# Kopfh_rerverst_rker_AmpBoard_Rev_1_0.net
KiCad netlist of a schematic drawn in EAGLE
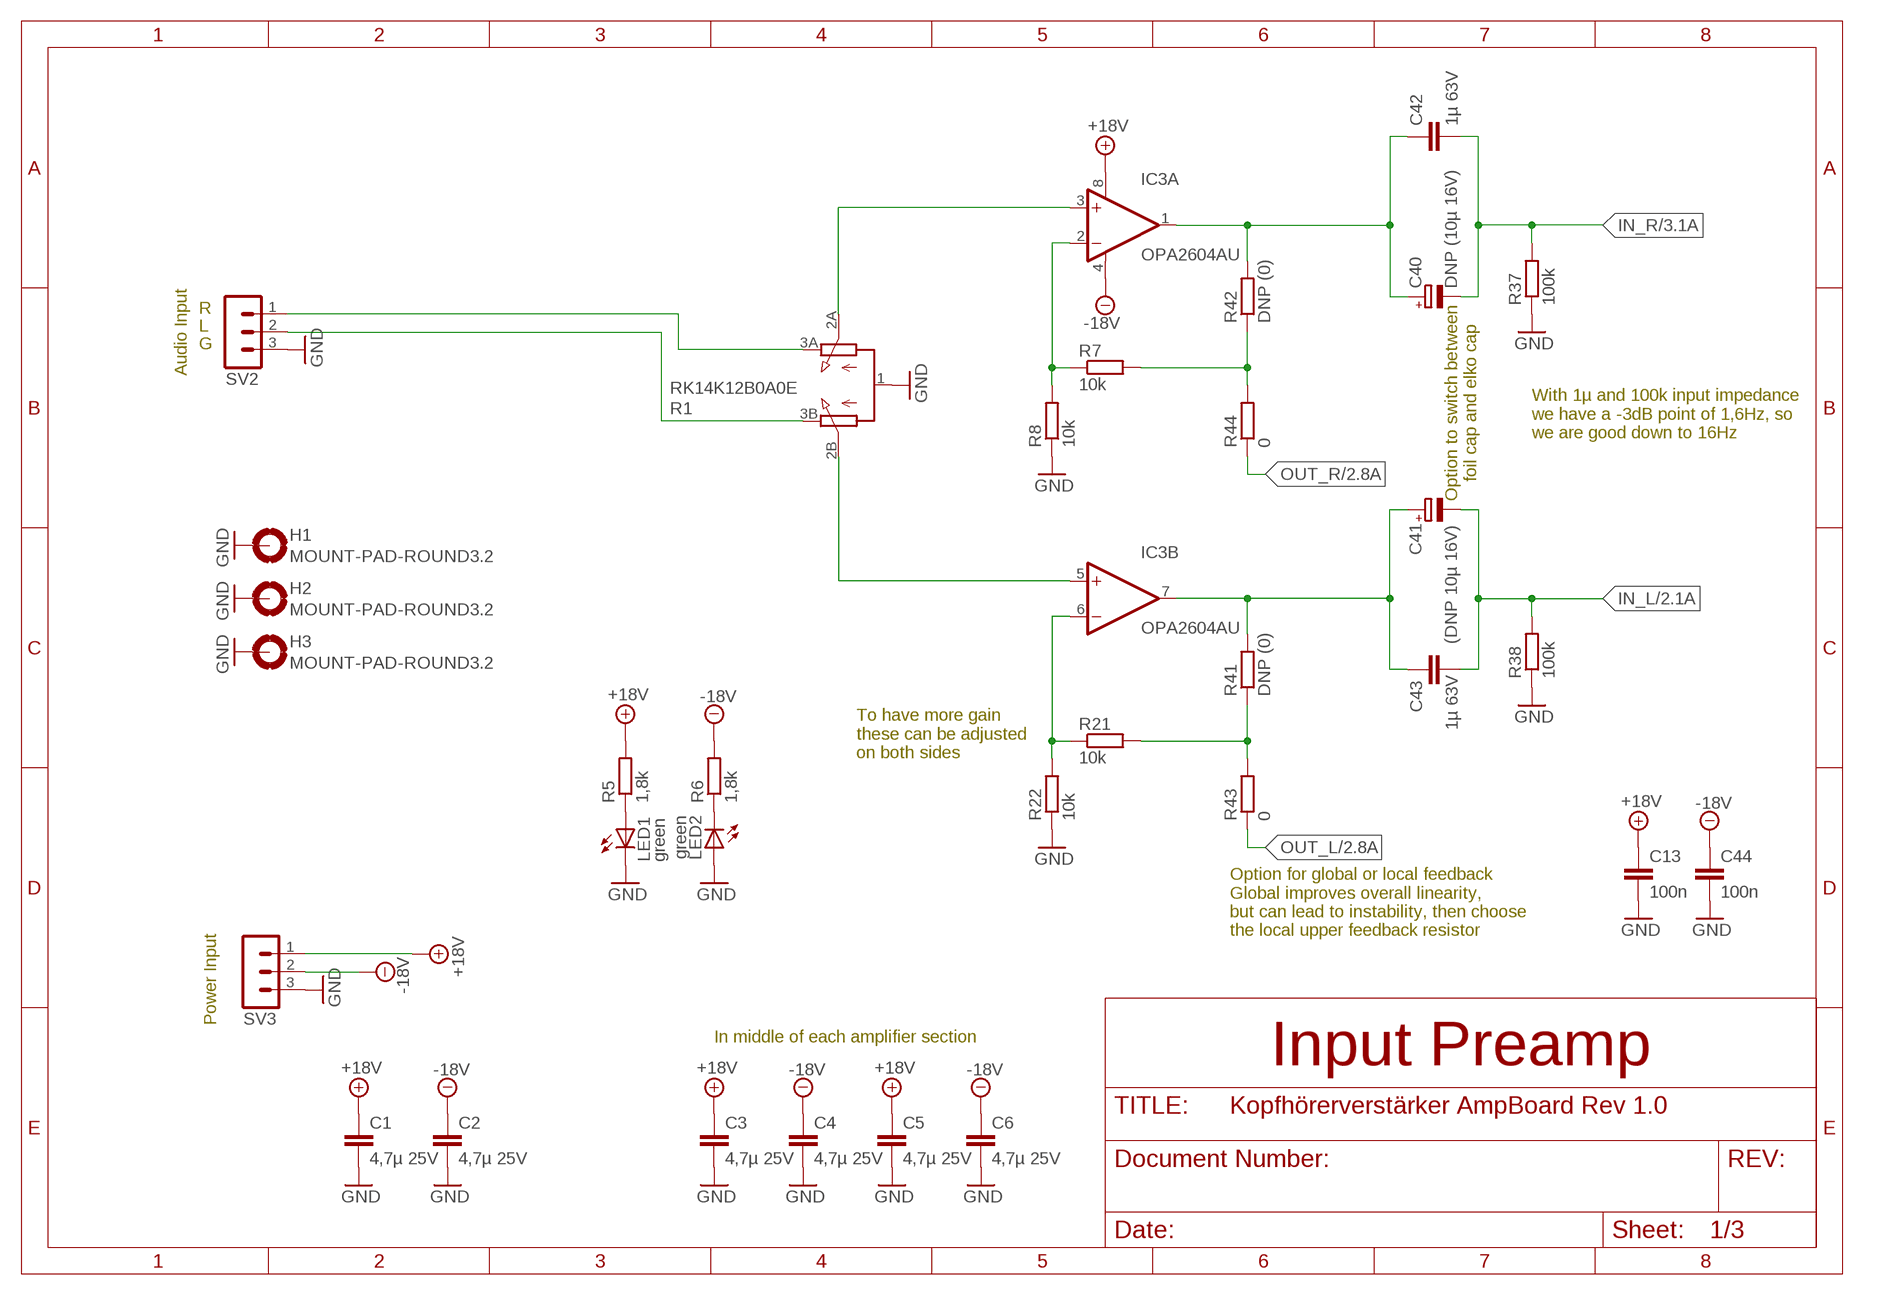
[diagram p0: schematic, sheet 1]
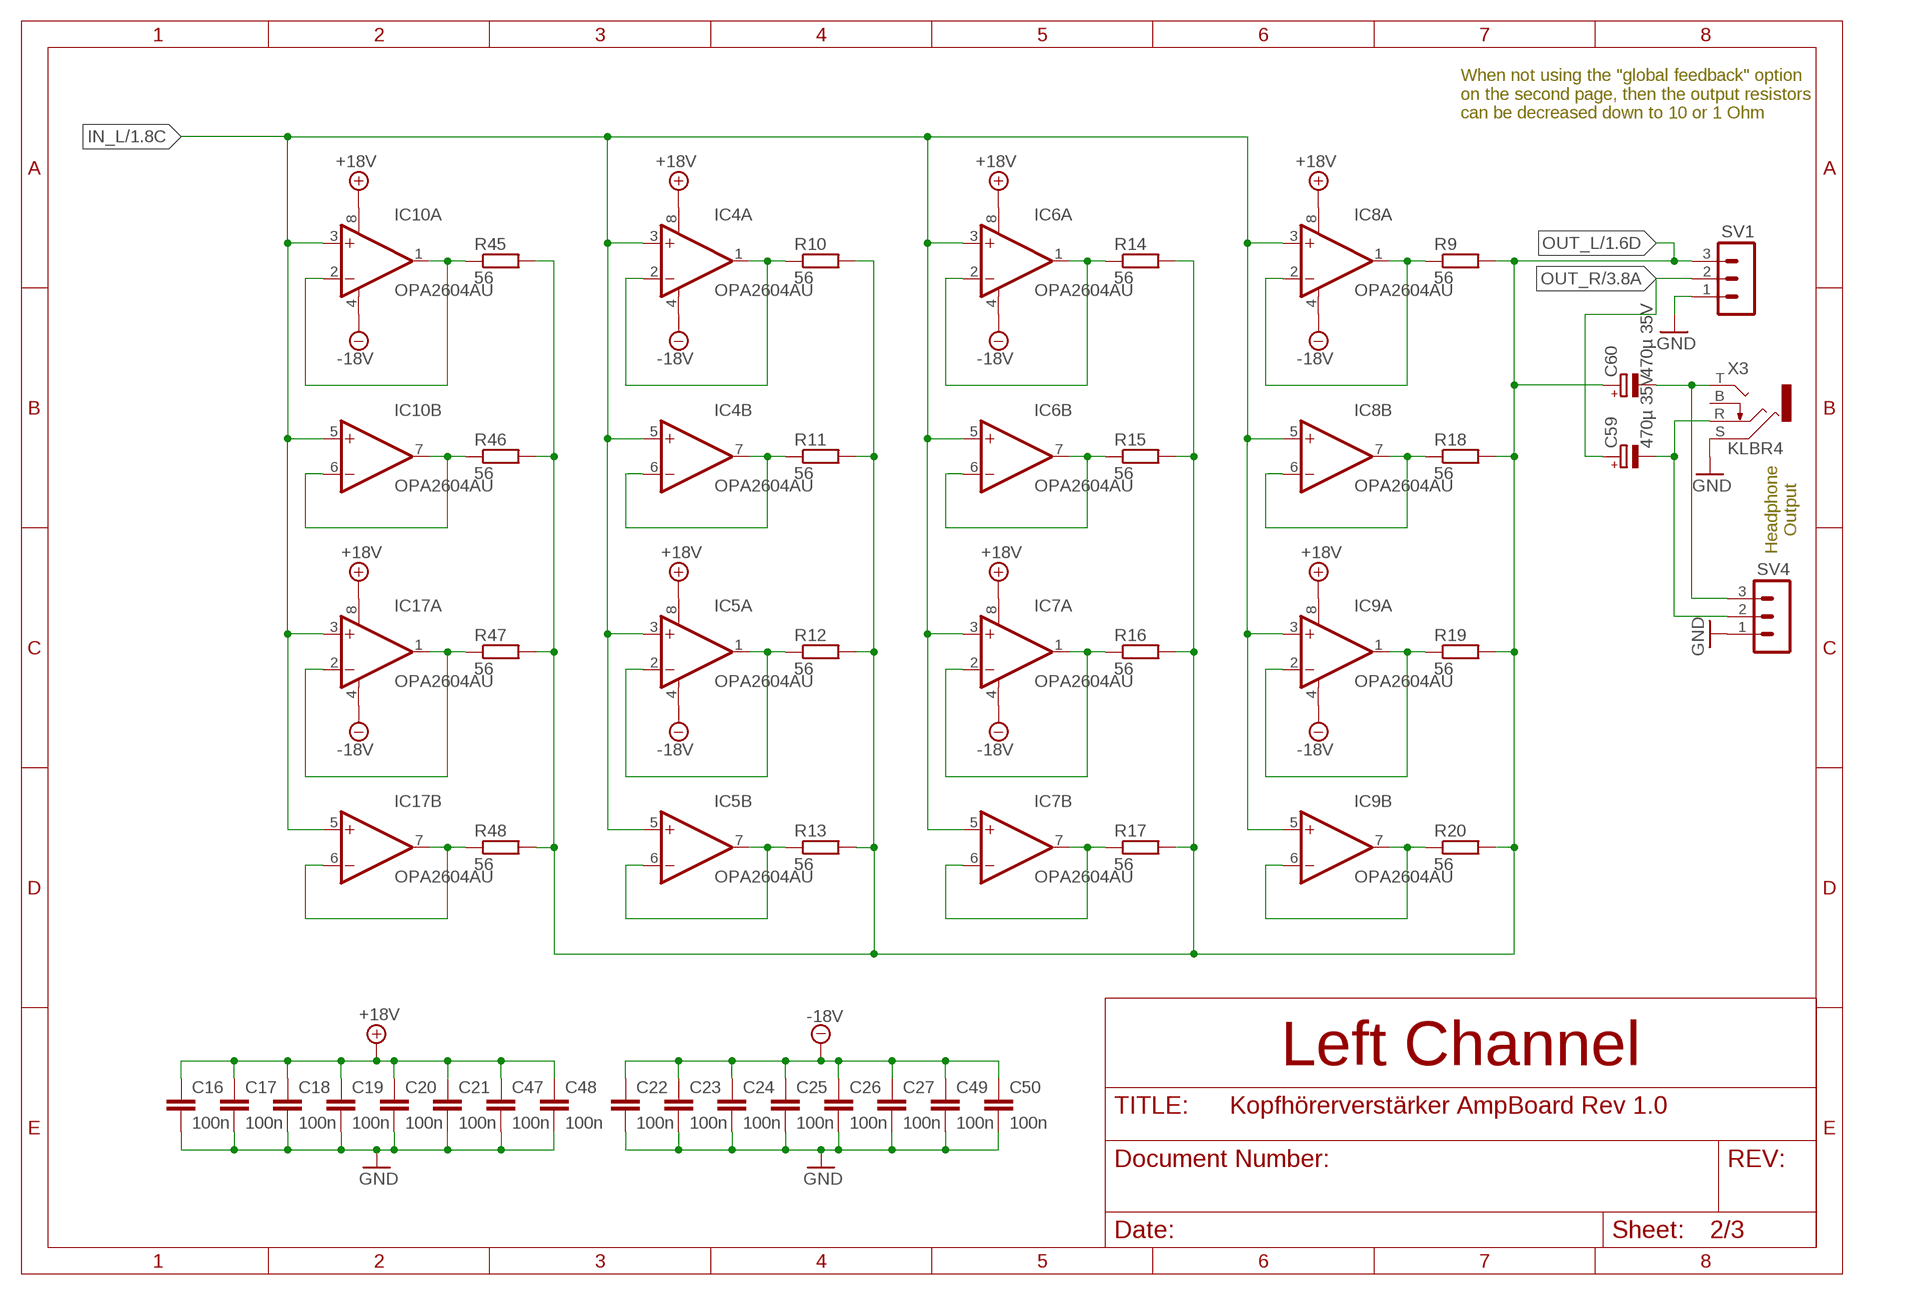
[diagram p1: schematic, sheet 2]
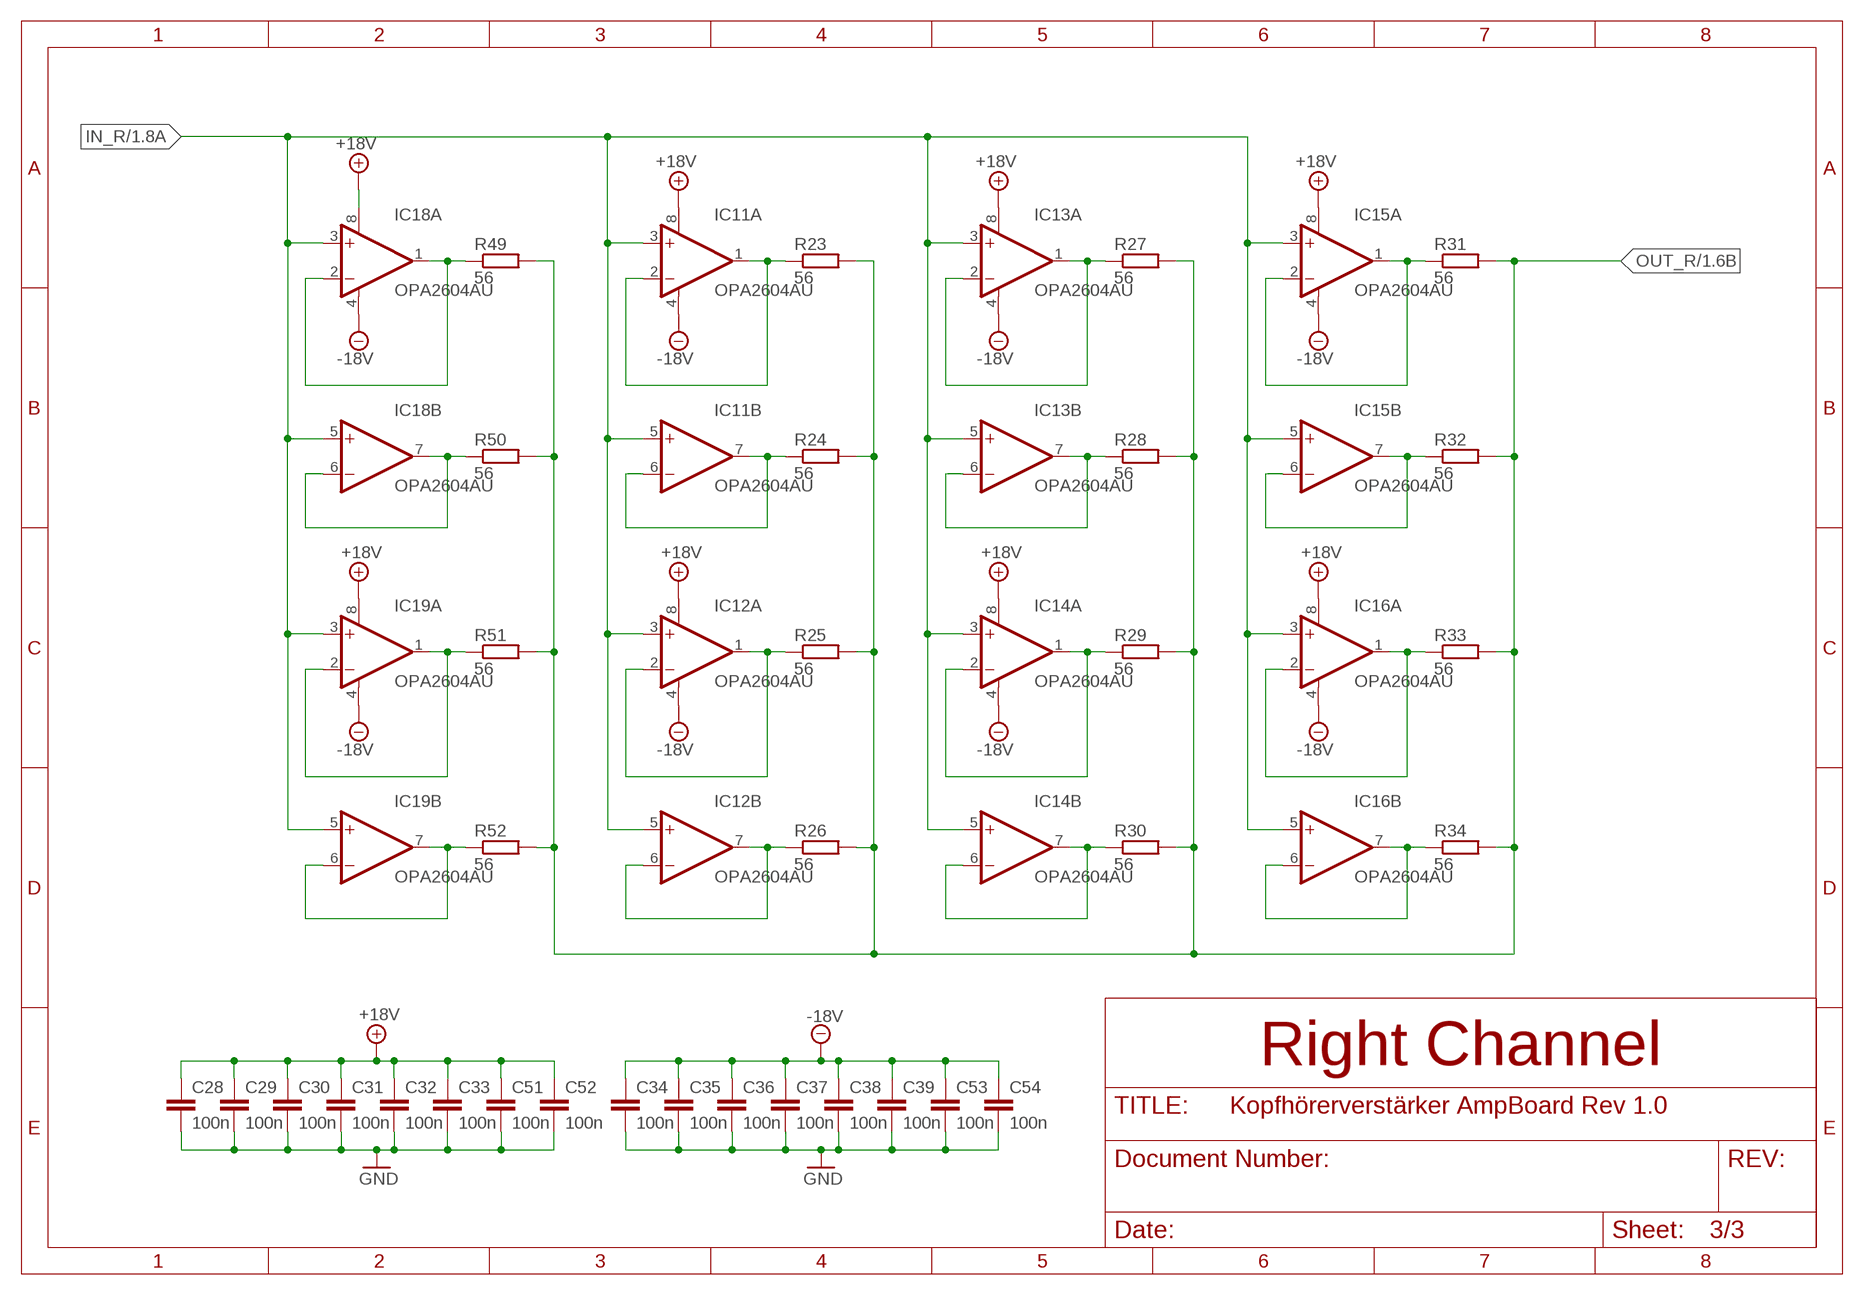
[diagram p2: schematic, sheet 3]

(export (version "E")
  (design (tool "Eeschema 10.0.6"))
  (components
    (comp (ref "C1")
      (value "4,7µ 25V")
      (footprint "eagle-import:C0805")
      (libsource (lib "eagle-import") (part "C-EUC0805"))
    )
    (comp (ref "C2")
      (value "4,7µ 25V")
      (footprint "eagle-import:C0805")
      (libsource (lib "eagle-import") (part "C-EUC0805"))
    )
    (comp (ref "C3")
      (value "4,7µ 25V")
      (footprint "eagle-import:C0805")
      (libsource (lib "eagle-import") (part "C-EUC0805"))
    )
    (comp (ref "C4")
      (value "4,7µ 25V")
      (footprint "eagle-import:C0805")
      (libsource (lib "eagle-import") (part "C-EUC0805"))
    )
    (comp (ref "C5")
      (value "4,7µ 25V")
      (footprint "eagle-import:C0805")
      (libsource (lib "eagle-import") (part "C-EUC0805"))
    )
    (comp (ref "C6")
      (value "4,7µ 25V")
      (footprint "eagle-import:C0805")
      (libsource (lib "eagle-import") (part "C-EUC0805"))
    )
    (comp (ref "C13")
      (value "100n")
      (footprint "eagle-import:C0805")
      (libsource (lib "eagle-import") (part "C-EUC0805"))
    )
    (comp (ref "C40")
      (value "DNP (10µ 16V)")
      (footprint "eagle-import:E2,5-5")
      (libsource (lib "eagle-import") (part "CPOL-EUE2.5-5"))
    )
    (comp (ref "C41")
      (value "(DNP 10µ 16V)")
      (footprint "eagle-import:E2,5-5")
      (libsource (lib "eagle-import") (part "CPOL-EUE2.5-5"))
    )
    (comp (ref "C42")
      (value "1µ 63V")
      (footprint "eagle-import:C050-050X075")
      (libsource (lib "eagle-import") (part "C-EU050-050X075"))
    )
    (comp (ref "C43")
      (value "1µ 63V")
      (footprint "eagle-import:C050-050X075")
      (libsource (lib "eagle-import") (part "C-EU050-050X075"))
    )
    (comp (ref "C44")
      (value "100n")
      (footprint "eagle-import:C0805")
      (libsource (lib "eagle-import") (part "C-EUC0805"))
    )
    (comp (ref "H1")
      (value "MOUNT-PAD-ROUND3.2")
      (footprint "eagle-import:3,2-PAD")
      (libsource (lib "eagle-import") (part "MOUNT-PAD-ROUND3.2"))
    )
    (comp (ref "H2")
      (value "MOUNT-PAD-ROUND3.2")
      (footprint "eagle-import:3,2-PAD")
      (libsource (lib "eagle-import") (part "MOUNT-PAD-ROUND3.2"))
    )
    (comp (ref "H3")
      (value "MOUNT-PAD-ROUND3.2")
      (footprint "eagle-import:3,2-PAD")
      (libsource (lib "eagle-import") (part "MOUNT-PAD-ROUND3.2"))
    )
    (comp (ref "IC3")
      (value "OPA2604AU")
      (footprint "eagle-import:SO08")
      (libsource (lib "eagle-import") (part "OPA2604AU"))
    )
    (comp (ref "LED1")
      (value "green")
      (footprint "eagle-import:LED3MM")
      (libsource (lib "eagle-import") (part "LED3MM"))
    )
    (comp (ref "LED2")
      (value "green")
      (footprint "eagle-import:LED3MM")
      (libsource (lib "eagle-import") (part "LED3MM"))
    )
    (comp (ref "R1")
      (value "RK14K12B0A0E")
      (footprint "eagle-import:RK14K12")
      (libsource (lib "eagle-import") (part "RK14K12X"))
    )
    (comp (ref "R5")
      (value "1,8k")
      (footprint "eagle-import:R0805")
      (libsource (lib "eagle-import") (part "R-EU_R0805"))
    )
    (comp (ref "R6")
      (value "1,8k")
      (footprint "eagle-import:R0805")
      (libsource (lib "eagle-import") (part "R-EU_R0805"))
    )
    (comp (ref "R7")
      (value "10k")
      (footprint "eagle-import:R0805")
      (libsource (lib "eagle-import") (part "R-EU_R0805"))
    )
    (comp (ref "R8")
      (value "10k")
      (footprint "eagle-import:R0805")
      (libsource (lib "eagle-import") (part "R-EU_R0805"))
    )
    (comp (ref "R21")
      (value "10k")
      (footprint "eagle-import:R0805")
      (libsource (lib "eagle-import") (part "R-EU_R0805"))
    )
    (comp (ref "R22")
      (value "10k")
      (footprint "eagle-import:R0805")
      (libsource (lib "eagle-import") (part "R-EU_R0805"))
    )
    (comp (ref "R37")
      (value "100k")
      (footprint "eagle-import:R0805")
      (libsource (lib "eagle-import") (part "R-EU_R0805"))
    )
    (comp (ref "R38")
      (value "100k")
      (footprint "eagle-import:R0805")
      (libsource (lib "eagle-import") (part "R-EU_R0805"))
    )
    (comp (ref "R41")
      (value "DNP (0)")
      (footprint "eagle-import:R0805")
      (libsource (lib "eagle-import") (part "R-EU_R0805"))
    )
    (comp (ref "R42")
      (value "DNP (0)")
      (footprint "eagle-import:R0805")
      (libsource (lib "eagle-import") (part "R-EU_R0805"))
    )
    (comp (ref "R43")
      (value "0")
      (footprint "eagle-import:R0805")
      (libsource (lib "eagle-import") (part "R-EU_R0805"))
    )
    (comp (ref "R44")
      (value "0")
      (footprint "eagle-import:R0805")
      (libsource (lib "eagle-import") (part "R-EU_R0805"))
    )
    (comp (ref "SV2")
      (value "MA03-1")
      (footprint "eagle-import:MA03-1")
      (libsource (lib "eagle-import") (part "MA03-1"))
    )
    (comp (ref "SV3")
      (value "MA03-1")
      (footprint "eagle-import:MA03-1")
      (libsource (lib "eagle-import") (part "MA03-1"))
    )
    (comp (ref "C16")
      (value "100n")
      (footprint "eagle-import:C0805")
      (libsource (lib "eagle-import") (part "C-EUC0805"))
    )
    (comp (ref "C17")
      (value "100n")
      (footprint "eagle-import:C0805")
      (libsource (lib "eagle-import") (part "C-EUC0805"))
    )
    (comp (ref "C18")
      (value "100n")
      (footprint "eagle-import:C0805")
      (libsource (lib "eagle-import") (part "C-EUC0805"))
    )
    (comp (ref "C19")
      (value "100n")
      (footprint "eagle-import:C0805")
      (libsource (lib "eagle-import") (part "C-EUC0805"))
    )
    (comp (ref "C20")
      (value "100n")
      (footprint "eagle-import:C0805")
      (libsource (lib "eagle-import") (part "C-EUC0805"))
    )
    (comp (ref "C21")
      (value "100n")
      (footprint "eagle-import:C0805")
      (libsource (lib "eagle-import") (part "C-EUC0805"))
    )
    (comp (ref "C22")
      (value "100n")
      (footprint "eagle-import:C0805")
      (libsource (lib "eagle-import") (part "C-EUC0805"))
    )
    (comp (ref "C23")
      (value "100n")
      (footprint "eagle-import:C0805")
      (libsource (lib "eagle-import") (part "C-EUC0805"))
    )
    (comp (ref "C24")
      (value "100n")
      (footprint "eagle-import:C0805")
      (libsource (lib "eagle-import") (part "C-EUC0805"))
    )
    (comp (ref "C25")
      (value "100n")
      (footprint "eagle-import:C0805")
      (libsource (lib "eagle-import") (part "C-EUC0805"))
    )
    (comp (ref "C26")
      (value "100n")
      (footprint "eagle-import:C0805")
      (libsource (lib "eagle-import") (part "C-EUC0805"))
    )
    (comp (ref "C27")
      (value "100n")
      (footprint "eagle-import:C0805")
      (libsource (lib "eagle-import") (part "C-EUC0805"))
    )
    (comp (ref "C47")
      (value "100n")
      (footprint "eagle-import:C0805")
      (libsource (lib "eagle-import") (part "C-EUC0805"))
    )
    (comp (ref "C48")
      (value "100n")
      (footprint "eagle-import:C0805")
      (libsource (lib "eagle-import") (part "C-EUC0805"))
    )
    (comp (ref "C49")
      (value "100n")
      (footprint "eagle-import:C0805")
      (libsource (lib "eagle-import") (part "C-EUC0805"))
    )
    (comp (ref "C50")
      (value "100n")
      (footprint "eagle-import:C0805")
      (libsource (lib "eagle-import") (part "C-EUC0805"))
    )
    (comp (ref "C59")
      (value "470µ 35V")
      (footprint "eagle-import:E5-10,5")
      (libsource (lib "eagle-import") (part "CPOL-EUE5-10.5"))
    )
    (comp (ref "C60")
      (value "470µ 35V")
      (footprint "eagle-import:E5-10,5")
      (libsource (lib "eagle-import") (part "CPOL-EUE5-10.5"))
    )
    (comp (ref "IC4")
      (value "OPA2604AU")
      (footprint "eagle-import:SO08")
      (libsource (lib "eagle-import") (part "OPA2604AU"))
    )
    (comp (ref "IC5")
      (value "OPA2604AU")
      (footprint "eagle-import:SO08")
      (libsource (lib "eagle-import") (part "OPA2604AU"))
    )
    (comp (ref "IC6")
      (value "OPA2604AU")
      (footprint "eagle-import:SO08")
      (libsource (lib "eagle-import") (part "OPA2604AU"))
    )
    (comp (ref "IC7")
      (value "OPA2604AU")
      (footprint "eagle-import:SO08")
      (libsource (lib "eagle-import") (part "OPA2604AU"))
    )
    (comp (ref "IC8")
      (value "OPA2604AU")
      (footprint "eagle-import:SO08")
      (libsource (lib "eagle-import") (part "OPA2604AU"))
    )
    (comp (ref "IC9")
      (value "OPA2604AU")
      (footprint "eagle-import:SO08")
      (libsource (lib "eagle-import") (part "OPA2604AU"))
    )
    (comp (ref "IC10")
      (value "OPA2604AU")
      (footprint "eagle-import:SO08")
      (libsource (lib "eagle-import") (part "OPA2604AU"))
    )
    (comp (ref "IC17")
      (value "OPA2604AU")
      (footprint "eagle-import:SO08")
      (libsource (lib "eagle-import") (part "OPA2604AU"))
    )
    (comp (ref "R9")
      (value "56")
      (footprint "eagle-import:R0805")
      (libsource (lib "eagle-import") (part "R-EU_R0805"))
    )
    (comp (ref "R10")
      (value "56")
      (footprint "eagle-import:R0805")
      (libsource (lib "eagle-import") (part "R-EU_R0805"))
    )
    (comp (ref "R11")
      (value "56")
      (footprint "eagle-import:R0805")
      (libsource (lib "eagle-import") (part "R-EU_R0805"))
    )
    (comp (ref "R12")
      (value "56")
      (footprint "eagle-import:R0805")
      (libsource (lib "eagle-import") (part "R-EU_R0805"))
    )
    (comp (ref "R13")
      (value "56")
      (footprint "eagle-import:R0805")
      (libsource (lib "eagle-import") (part "R-EU_R0805"))
    )
    (comp (ref "R14")
      (value "56")
      (footprint "eagle-import:R0805")
      (libsource (lib "eagle-import") (part "R-EU_R0805"))
    )
    (comp (ref "R15")
      (value "56")
      (footprint "eagle-import:R0805")
      (libsource (lib "eagle-import") (part "R-EU_R0805"))
    )
    (comp (ref "R16")
      (value "56")
      (footprint "eagle-import:R0805")
      (libsource (lib "eagle-import") (part "R-EU_R0805"))
    )
    (comp (ref "R17")
      (value "56")
      (footprint "eagle-import:R0805")
      (libsource (lib "eagle-import") (part "R-EU_R0805"))
    )
    (comp (ref "R18")
      (value "56")
      (footprint "eagle-import:R0805")
      (libsource (lib "eagle-import") (part "R-EU_R0805"))
    )
    (comp (ref "R19")
      (value "56")
      (footprint "eagle-import:R0805")
      (libsource (lib "eagle-import") (part "R-EU_R0805"))
    )
    (comp (ref "R20")
      (value "56")
      (footprint "eagle-import:R0805")
      (libsource (lib "eagle-import") (part "R-EU_R0805"))
    )
    (comp (ref "R45")
      (value "56")
      (footprint "eagle-import:R0805")
      (libsource (lib "eagle-import") (part "R-EU_R0805"))
    )
    (comp (ref "R46")
      (value "56")
      (footprint "eagle-import:R0805")
      (libsource (lib "eagle-import") (part "R-EU_R0805"))
    )
    (comp (ref "R47")
      (value "56")
      (footprint "eagle-import:R0805")
      (libsource (lib "eagle-import") (part "R-EU_R0805"))
    )
    (comp (ref "R48")
      (value "56")
      (footprint "eagle-import:R0805")
      (libsource (lib "eagle-import") (part "R-EU_R0805"))
    )
    (comp (ref "SV1")
      (value "MA03-1")
      (footprint "eagle-import:MA03-1")
      (libsource (lib "eagle-import") (part "MA03-1"))
    )
    (comp (ref "SV4")
      (value "MA03-1")
      (footprint "eagle-import:MA03-1")
      (libsource (lib "eagle-import") (part "MA03-1"))
    )
    (comp (ref "X3")
      (value "KLBR4")
      (footprint "eagle-import:KLBR4")
      (fields (field (name "MPN") "KLBR 4"))
      (libsource (lib "eagle-import") (part "KLBR4"))
    )
    (comp (ref "C28")
      (value "100n")
      (footprint "eagle-import:C0805")
      (libsource (lib "eagle-import") (part "C-EUC0805"))
    )
    (comp (ref "C29")
      (value "100n")
      (footprint "eagle-import:C0805")
      (libsource (lib "eagle-import") (part "C-EUC0805"))
    )
    (comp (ref "C30")
      (value "100n")
      (footprint "eagle-import:C0805")
      (libsource (lib "eagle-import") (part "C-EUC0805"))
    )
    (comp (ref "C31")
      (value "100n")
      (footprint "eagle-import:C0805")
      (libsource (lib "eagle-import") (part "C-EUC0805"))
    )
    (comp (ref "C32")
      (value "100n")
      (footprint "eagle-import:C0805")
      (libsource (lib "eagle-import") (part "C-EUC0805"))
    )
    (comp (ref "C33")
      (value "100n")
      (footprint "eagle-import:C0805")
      (libsource (lib "eagle-import") (part "C-EUC0805"))
    )
    (comp (ref "C34")
      (value "100n")
      (footprint "eagle-import:C0805")
      (libsource (lib "eagle-import") (part "C-EUC0805"))
    )
    (comp (ref "C35")
      (value "100n")
      (footprint "eagle-import:C0805")
      (libsource (lib "eagle-import") (part "C-EUC0805"))
    )
    (comp (ref "C36")
      (value "100n")
      (footprint "eagle-import:C0805")
      (libsource (lib "eagle-import") (part "C-EUC0805"))
    )
    (comp (ref "C37")
      (value "100n")
      (footprint "eagle-import:C0805")
      (libsource (lib "eagle-import") (part "C-EUC0805"))
    )
    (comp (ref "C38")
      (value "100n")
      (footprint "eagle-import:C0805")
      (libsource (lib "eagle-import") (part "C-EUC0805"))
    )
    (comp (ref "C39")
      (value "100n")
      (footprint "eagle-import:C0805")
      (libsource (lib "eagle-import") (part "C-EUC0805"))
    )
    (comp (ref "C51")
      (value "100n")
      (footprint "eagle-import:C0805")
      (libsource (lib "eagle-import") (part "C-EUC0805"))
    )
    (comp (ref "C52")
      (value "100n")
      (footprint "eagle-import:C0805")
      (libsource (lib "eagle-import") (part "C-EUC0805"))
    )
    (comp (ref "C53")
      (value "100n")
      (footprint "eagle-import:C0805")
      (libsource (lib "eagle-import") (part "C-EUC0805"))
    )
    (comp (ref "C54")
      (value "100n")
      (footprint "eagle-import:C0805")
      (libsource (lib "eagle-import") (part "C-EUC0805"))
    )
    (comp (ref "IC11")
      (value "OPA2604AU")
      (footprint "eagle-import:SO08")
      (libsource (lib "eagle-import") (part "OPA2604AU"))
    )
    (comp (ref "IC12")
      (value "OPA2604AU")
      (footprint "eagle-import:SO08")
      (libsource (lib "eagle-import") (part "OPA2604AU"))
    )
    (comp (ref "IC13")
      (value "OPA2604AU")
      (footprint "eagle-import:SO08")
      (libsource (lib "eagle-import") (part "OPA2604AU"))
    )
    (comp (ref "IC14")
      (value "OPA2604AU")
      (footprint "eagle-import:SO08")
      (libsource (lib "eagle-import") (part "OPA2604AU"))
    )
    (comp (ref "IC15")
      (value "OPA2604AU")
      (footprint "eagle-import:SO08")
      (libsource (lib "eagle-import") (part "OPA2604AU"))
    )
    (comp (ref "IC16")
      (value "OPA2604AU")
      (footprint "eagle-import:SO08")
      (libsource (lib "eagle-import") (part "OPA2604AU"))
    )
    (comp (ref "IC18")
      (value "OPA2604AU")
      (footprint "eagle-import:SO08")
      (libsource (lib "eagle-import") (part "OPA2604AU"))
    )
    (comp (ref "IC19")
      (value "OPA2604AU")
      (footprint "eagle-import:SO08")
      (libsource (lib "eagle-import") (part "OPA2604AU"))
    )
    (comp (ref "R23")
      (value "56")
      (footprint "eagle-import:R0805")
      (libsource (lib "eagle-import") (part "R-EU_R0805"))
    )
    (comp (ref "R24")
      (value "56")
      (footprint "eagle-import:R0805")
      (libsource (lib "eagle-import") (part "R-EU_R0805"))
    )
    (comp (ref "R25")
      (value "56")
      (footprint "eagle-import:R0805")
      (libsource (lib "eagle-import") (part "R-EU_R0805"))
    )
    (comp (ref "R26")
      (value "56")
      (footprint "eagle-import:R0805")
      (libsource (lib "eagle-import") (part "R-EU_R0805"))
    )
    (comp (ref "R27")
      (value "56")
      (footprint "eagle-import:R0805")
      (libsource (lib "eagle-import") (part "R-EU_R0805"))
    )
    (comp (ref "R28")
      (value "56")
      (footprint "eagle-import:R0805")
      (libsource (lib "eagle-import") (part "R-EU_R0805"))
    )
    (comp (ref "R29")
      (value "56")
      (footprint "eagle-import:R0805")
      (libsource (lib "eagle-import") (part "R-EU_R0805"))
    )
    (comp (ref "R30")
      (value "56")
      (footprint "eagle-import:R0805")
      (libsource (lib "eagle-import") (part "R-EU_R0805"))
    )
    (comp (ref "R31")
      (value "56")
      (footprint "eagle-import:R0805")
      (libsource (lib "eagle-import") (part "R-EU_R0805"))
    )
    (comp (ref "R32")
      (value "56")
      (footprint "eagle-import:R0805")
      (libsource (lib "eagle-import") (part "R-EU_R0805"))
    )
    (comp (ref "R33")
      (value "56")
      (footprint "eagle-import:R0805")
      (libsource (lib "eagle-import") (part "R-EU_R0805"))
    )
    (comp (ref "R34")
      (value "56")
      (footprint "eagle-import:R0805")
      (libsource (lib "eagle-import") (part "R-EU_R0805"))
    )
    (comp (ref "R49")
      (value "56")
      (footprint "eagle-import:R0805")
      (libsource (lib "eagle-import") (part "R-EU_R0805"))
    )
    (comp (ref "R50")
      (value "56")
      (footprint "eagle-import:R0805")
      (libsource (lib "eagle-import") (part "R-EU_R0805"))
    )
    (comp (ref "R51")
      (value "56")
      (footprint "eagle-import:R0805")
      (libsource (lib "eagle-import") (part "R-EU_R0805"))
    )
    (comp (ref "R52")
      (value "56")
      (footprint "eagle-import:R0805")
      (libsource (lib "eagle-import") (part "R-EU_R0805"))
    )
  )
  (nets
    (net (code "1") (name "+18V") (class "Default")
      (node (ref "C1") (pin "1") (pinfunction "1_1") (pintype "passive"))
      (node (ref "C13") (pin "1") (pinfunction "1_1") (pintype "passive"))
      (node (ref "C16") (pin "1") (pinfunction "1_1") (pintype "passive"))
      (node (ref "C17") (pin "1") (pinfunction "1_1") (pintype "passive"))
      (node (ref "C18") (pin "1") (pinfunction "1_1") (pintype "passive"))
      (node (ref "C19") (pin "1") (pinfunction "1_1") (pintype "passive"))
      (node (ref "C20") (pin "1") (pinfunction "1_1") (pintype "passive"))
      (node (ref "C21") (pin "1") (pinfunction "1_1") (pintype "passive"))
      (node (ref "C28") (pin "1") (pinfunction "1_1") (pintype "passive"))
      (node (ref "C29") (pin "1") (pinfunction "1_1") (pintype "passive"))
      (node (ref "C3") (pin "1") (pinfunction "1_1") (pintype "passive"))
      (node (ref "C30") (pin "1") (pinfunction "1_1") (pintype "passive"))
      (node (ref "C31") (pin "1") (pinfunction "1_1") (pintype "passive"))
      (node (ref "C32") (pin "1") (pinfunction "1_1") (pintype "passive"))
      (node (ref "C33") (pin "1") (pinfunction "1_1") (pintype "passive"))
      (node (ref "C47") (pin "1") (pinfunction "1_1") (pintype "passive"))
      (node (ref "C48") (pin "1") (pinfunction "1_1") (pintype "passive"))
      (node (ref "C5") (pin "1") (pinfunction "1_1") (pintype "passive"))
      (node (ref "C51") (pin "1") (pinfunction "1_1") (pintype "passive"))
      (node (ref "C52") (pin "1") (pinfunction "1_1") (pintype "passive"))
      (node (ref "IC10") (pin "8") (pinfunction "V+_8") (pintype "power_in"))
      (node (ref "IC11") (pin "8") (pinfunction "V+_8") (pintype "power_in"))
      (node (ref "IC12") (pin "8") (pinfunction "V+_8") (pintype "power_in"))
      (node (ref "IC13") (pin "8") (pinfunction "V+_8") (pintype "power_in"))
      (node (ref "IC14") (pin "8") (pinfunction "V+_8") (pintype "power_in"))
      (node (ref "IC15") (pin "8") (pinfunction "V+_8") (pintype "power_in"))
      (node (ref "IC16") (pin "8") (pinfunction "V+_8") (pintype "power_in"))
      (node (ref "IC17") (pin "8") (pinfunction "V+_8") (pintype "power_in"))
      (node (ref "IC18") (pin "8") (pinfunction "V+_8") (pintype "power_in"))
      (node (ref "IC19") (pin "8") (pinfunction "V+_8") (pintype "power_in"))
      (node (ref "IC3") (pin "8") (pinfunction "V+_8") (pintype "power_in"))
      (node (ref "IC4") (pin "8") (pinfunction "V+_8") (pintype "power_in"))
      (node (ref "IC5") (pin "8") (pinfunction "V+_8") (pintype "power_in"))
      (node (ref "IC6") (pin "8") (pinfunction "V+_8") (pintype "power_in"))
      (node (ref "IC7") (pin "8") (pinfunction "V+_8") (pintype "power_in"))
      (node (ref "IC8") (pin "8") (pinfunction "V+_8") (pintype "power_in"))
      (node (ref "IC9") (pin "8") (pinfunction "V+_8") (pintype "power_in"))
      (node (ref "R5") (pin "2") (pinfunction "2_2") (pintype "passive"))
      (node (ref "SV3") (pin "1") (pinfunction "1_1") (pintype "passive"))
    )
    (net (code "2") (name "-18V") (class "Default")
      (node (ref "C2") (pin "1") (pinfunction "1_1") (pintype "passive"))
      (node (ref "C22") (pin "1") (pinfunction "1_1") (pintype "passive"))
      (node (ref "C23") (pin "1") (pinfunction "1_1") (pintype "passive"))
      (node (ref "C24") (pin "1") (pinfunction "1_1") (pintype "passive"))
      (node (ref "C25") (pin "1") (pinfunction "1_1") (pintype "passive"))
      (node (ref "C26") (pin "1") (pinfunction "1_1") (pintype "passive"))
      (node (ref "C27") (pin "1") (pinfunction "1_1") (pintype "passive"))
      (node (ref "C34") (pin "1") (pinfunction "1_1") (pintype "passive"))
      (node (ref "C35") (pin "1") (pinfunction "1_1") (pintype "passive"))
      (node (ref "C36") (pin "1") (pinfunction "1_1") (pintype "passive"))
      (node (ref "C37") (pin "1") (pinfunction "1_1") (pintype "passive"))
      (node (ref "C38") (pin "1") (pinfunction "1_1") (pintype "passive"))
      (node (ref "C39") (pin "1") (pinfunction "1_1") (pintype "passive"))
      (node (ref "C4") (pin "1") (pinfunction "1_1") (pintype "passive"))
      (node (ref "C44") (pin "1") (pinfunction "1_1") (pintype "passive"))
      (node (ref "C49") (pin "1") (pinfunction "1_1") (pintype "passive"))
      (node (ref "C50") (pin "1") (pinfunction "1_1") (pintype "passive"))
      (node (ref "C53") (pin "1") (pinfunction "1_1") (pintype "passive"))
      (node (ref "C54") (pin "1") (pinfunction "1_1") (pintype "passive"))
      (node (ref "C6") (pin "1") (pinfunction "1_1") (pintype "passive"))
      (node (ref "IC10") (pin "4") (pinfunction "V-_4") (pintype "power_in"))
      (node (ref "IC11") (pin "4") (pinfunction "V-_4") (pintype "power_in"))
      (node (ref "IC12") (pin "4") (pinfunction "V-_4") (pintype "power_in"))
      (node (ref "IC13") (pin "4") (pinfunction "V-_4") (pintype "power_in"))
      (node (ref "IC14") (pin "4") (pinfunction "V-_4") (pintype "power_in"))
      (node (ref "IC15") (pin "4") (pinfunction "V-_4") (pintype "power_in"))
      (node (ref "IC16") (pin "4") (pinfunction "V-_4") (pintype "power_in"))
      (node (ref "IC17") (pin "4") (pinfunction "V-_4") (pintype "power_in"))
      (node (ref "IC18") (pin "4") (pinfunction "V-_4") (pintype "power_in"))
      (node (ref "IC19") (pin "4") (pinfunction "V-_4") (pintype "power_in"))
      (node (ref "IC3") (pin "4") (pinfunction "V-_4") (pintype "power_in"))
      (node (ref "IC4") (pin "4") (pinfunction "V-_4") (pintype "power_in"))
      (node (ref "IC5") (pin "4") (pinfunction "V-_4") (pintype "power_in"))
      (node (ref "IC6") (pin "4") (pinfunction "V-_4") (pintype "power_in"))
      (node (ref "IC7") (pin "4") (pinfunction "V-_4") (pintype "power_in"))
      (node (ref "IC8") (pin "4") (pinfunction "V-_4") (pintype "power_in"))
      (node (ref "IC9") (pin "4") (pinfunction "V-_4") (pintype "power_in"))
      (node (ref "R6") (pin "2") (pinfunction "2_2") (pintype "passive"))
      (node (ref "SV3") (pin "2") (pinfunction "2_2") (pintype "passive"))
    )
    (net (code "3") (name "GND") (class "Default")
      (node (ref "C1") (pin "2") (pinfunction "2_2") (pintype "passive"))
      (node (ref "C13") (pin "2") (pinfunction "2_2") (pintype "passive"))
      (node (ref "C16") (pin "2") (pinfunction "2_2") (pintype "passive"))
      (node (ref "C17") (pin "2") (pinfunction "2_2") (pintype "passive"))
      (node (ref "C18") (pin "2") (pinfunction "2_2") (pintype "passive"))
      (node (ref "C19") (pin "2") (pinfunction "2_2") (pintype "passive"))
      (node (ref "C2") (pin "2") (pinfunction "2_2") (pintype "passive"))
      (node (ref "C20") (pin "2") (pinfunction "2_2") (pintype "passive"))
      (node (ref "C21") (pin "2") (pinfunction "2_2") (pintype "passive"))
      (node (ref "C22") (pin "2") (pinfunction "2_2") (pintype "passive"))
      (node (ref "C23") (pin "2") (pinfunction "2_2") (pintype "passive"))
      (node (ref "C24") (pin "2") (pinfunction "2_2") (pintype "passive"))
      (node (ref "C25") (pin "2") (pinfunction "2_2") (pintype "passive"))
      (node (ref "C26") (pin "2") (pinfunction "2_2") (pintype "passive"))
      (node (ref "C27") (pin "2") (pinfunction "2_2") (pintype "passive"))
      (node (ref "C28") (pin "2") (pinfunction "2_2") (pintype "passive"))
      (node (ref "C29") (pin "2") (pinfunction "2_2") (pintype "passive"))
      (node (ref "C3") (pin "2") (pinfunction "2_2") (pintype "passive"))
      (node (ref "C30") (pin "2") (pinfunction "2_2") (pintype "passive"))
      (node (ref "C31") (pin "2") (pinfunction "2_2") (pintype "passive"))
      (node (ref "C32") (pin "2") (pinfunction "2_2") (pintype "passive"))
      (node (ref "C33") (pin "2") (pinfunction "2_2") (pintype "passive"))
      (node (ref "C34") (pin "2") (pinfunction "2_2") (pintype "passive"))
      (node (ref "C35") (pin "2") (pinfunction "2_2") (pintype "passive"))
      (node (ref "C36") (pin "2") (pinfunction "2_2") (pintype "passive"))
      (node (ref "C37") (pin "2") (pinfunction "2_2") (pintype "passive"))
      (node (ref "C38") (pin "2") (pinfunction "2_2") (pintype "passive"))
      (node (ref "C39") (pin "2") (pinfunction "2_2") (pintype "passive"))
      (node (ref "C4") (pin "2") (pinfunction "2_2") (pintype "passive"))
      (node (ref "C44") (pin "2") (pinfunction "2_2") (pintype "passive"))
      (node (ref "C47") (pin "2") (pinfunction "2_2") (pintype "passive"))
      (node (ref "C48") (pin "2") (pinfunction "2_2") (pintype "passive"))
      (node (ref "C49") (pin "2") (pinfunction "2_2") (pintype "passive"))
      (node (ref "C5") (pin "2") (pinfunction "2_2") (pintype "passive"))
      (node (ref "C50") (pin "2") (pinfunction "2_2") (pintype "passive"))
      (node (ref "C51") (pin "2") (pinfunction "2_2") (pintype "passive"))
      (node (ref "C52") (pin "2") (pinfunction "2_2") (pintype "passive"))
      (node (ref "C53") (pin "2") (pinfunction "2_2") (pintype "passive"))
      (node (ref "C54") (pin "2") (pinfunction "2_2") (pintype "passive"))
      (node (ref "C6") (pin "2") (pinfunction "2_2") (pintype "passive"))
      (node (ref "H1") (pin "B3,2") (pinfunction "MOUNT_B3,2") (pintype "passive"))
      (node (ref "H2") (pin "B3,2") (pinfunction "MOUNT_B3,2") (pintype "passive"))
      (node (ref "H3") (pin "B3,2") (pinfunction "MOUNT_B3,2") (pintype "passive"))
      (node (ref "LED1") (pin "K") (pinfunction "C_K") (pintype "passive"))
      (node (ref "LED2") (pin "A") (pinfunction "A_A") (pintype "passive"))
      (node (ref "R1") (pin "1") (pinfunction "1_1") (pintype "passive"))
      (node (ref "R22") (pin "1") (pinfunction "1_1") (pintype "passive"))
      (node (ref "R37") (pin "1") (pinfunction "1_1") (pintype "passive"))
      (node (ref "R38") (pin "1") (pinfunction "1_1") (pintype "passive"))
      (node (ref "R8") (pin "1") (pinfunction "1_1") (pintype "passive"))
      (node (ref "SV1") (pin "1") (pinfunction "1_1") (pintype "passive"))
      (node (ref "SV2") (pin "3") (pinfunction "3_3") (pintype "passive"))
      (node (ref "SV3") (pin "3") (pinfunction "3_3") (pintype "passive"))
      (node (ref "SV4") (pin "1") (pinfunction "1_1") (pintype "passive"))
      (node (ref "X3") (pin "S") (pinfunction "S_S") (pintype "passive"))
    )
    (net (code "4") (name "IN_L") (class "Default")
      (node (ref "C41") (pin "-") (pinfunction "-_-") (pintype "passive"))
      (node (ref "C43") (pin "2") (pinfunction "2_2") (pintype "passive"))
      (node (ref "IC10") (pin "3") (pinfunction "+IN_3") (pintype "input"))
      (node (ref "IC10") (pin "5") (pinfunction "+IN_5") (pintype "input"))
      (node (ref "IC17") (pin "3") (pinfunction "+IN_3") (pintype "input"))
      (node (ref "IC17") (pin "5") (pinfunction "+IN_5") (pintype "input"))
      (node (ref "IC4") (pin "3") (pinfunction "+IN_3") (pintype "input"))
      (node (ref "IC4") (pin "5") (pinfunction "+IN_5") (pintype "input"))
      (node (ref "IC5") (pin "3") (pinfunction "+IN_3") (pintype "input"))
      (node (ref "IC5") (pin "5") (pinfunction "+IN_5") (pintype "input"))
      (node (ref "IC6") (pin "3") (pinfunction "+IN_3") (pintype "input"))
      (node (ref "IC6") (pin "5") (pinfunction "+IN_5") (pintype "input"))
      (node (ref "IC7") (pin "3") (pinfunction "+IN_3") (pintype "input"))
      (node (ref "IC7") (pin "5") (pinfunction "+IN_5") (pintype "input"))
      (node (ref "IC8") (pin "3") (pinfunction "+IN_3") (pintype "input"))
      (node (ref "IC8") (pin "5") (pinfunction "+IN_5") (pintype "input"))
      (node (ref "IC9") (pin "3") (pinfunction "+IN_3") (pintype "input"))
      (node (ref "IC9") (pin "5") (pinfunction "+IN_5") (pintype "input"))
      (node (ref "R38") (pin "2") (pinfunction "2_2") (pintype "passive"))
    )
    (net (code "5") (name "IN_R") (class "Default")
      (node (ref "C40") (pin "-") (pinfunction "-_-") (pintype "passive"))
      (node (ref "C42") (pin "2") (pinfunction "2_2") (pintype "passive"))
      (node (ref "IC11") (pin "3") (pinfunction "+IN_3") (pintype "input"))
      (node (ref "IC11") (pin "5") (pinfunction "+IN_5") (pintype "input"))
      (node (ref "IC12") (pin "3") (pinfunction "+IN_3") (pintype "input"))
      (node (ref "IC12") (pin "5") (pinfunction "+IN_5") (pintype "input"))
      (node (ref "IC13") (pin "3") (pinfunction "+IN_3") (pintype "input"))
      (node (ref "IC13") (pin "5") (pinfunction "+IN_5") (pintype "input"))
      (node (ref "IC14") (pin "3") (pinfunction "+IN_3") (pintype "input"))
      (node (ref "IC14") (pin "5") (pinfunction "+IN_5") (pintype "input"))
      (node (ref "IC15") (pin "3") (pinfunction "+IN_3") (pintype "input"))
      (node (ref "IC15") (pin "5") (pinfunction "+IN_5") (pintype "input"))
      (node (ref "IC16") (pin "3") (pinfunction "+IN_3") (pintype "input"))
      (node (ref "IC16") (pin "5") (pinfunction "+IN_5") (pintype "input"))
      (node (ref "IC18") (pin "3") (pinfunction "+IN_3") (pintype "input"))
      (node (ref "IC18") (pin "5") (pinfunction "+IN_5") (pintype "input"))
      (node (ref "IC19") (pin "3") (pinfunction "+IN_3") (pintype "input"))
      (node (ref "IC19") (pin "5") (pinfunction "+IN_5") (pintype "input"))
      (node (ref "R37") (pin "2") (pinfunction "2_2") (pintype "passive"))
    )
    (net (code "6") (name "Net-(C59-Pad-)") (class "Default")
      (node (ref "C59") (pin "-") (pinfunction "-_-") (pintype "passive"))
      (node (ref "SV4") (pin "2") (pinfunction "2_2") (pintype "passive"))
      (node (ref "X3") (pin "R") (pinfunction "R_R") (pintype "passive"))
    )
    (net (code "7") (name "Net-(C60-Pad-)") (class "Default")
      (node (ref "C60") (pin "-") (pinfunction "-_-") (pintype "passive"))
      (node (ref "SV4") (pin "3") (pinfunction "3_3") (pintype "passive"))
      (node (ref "X3") (pin "T") (pinfunction "T_T") (pintype "passive"))
    )
    (net (code "8") (name "Net-(IC3A-+IN)") (class "Default")
      (node (ref "IC3") (pin "3") (pinfunction "+IN_3") (pintype "input"))
      (node (ref "R1") (pin "2A") (pinfunction "2A_2A") (pintype "passive"))
    )
    (net (code "9") (name "Net-(IC3A--IN)") (class "Default")
      (node (ref "IC3") (pin "2") (pinfunction "-IN_2") (pintype "input"))
      (node (ref "R7") (pin "1") (pinfunction "1_1") (pintype "passive"))
      (node (ref "R8") (pin "2") (pinfunction "2_2") (pintype "passive"))
    )
    (net (code "10") (name "Net-(IC3A-OUT)") (class "Default")
      (node (ref "C40") (pin "+") (pinfunction "+_+") (pintype "passive"))
      (node (ref "C42") (pin "1") (pinfunction "1_1") (pintype "passive"))
      (node (ref "IC3") (pin "1") (pinfunction "OUT_1") (pintype "output"))
      (node (ref "R42") (pin "2") (pinfunction "2_2") (pintype "passive"))
    )
    (net (code "11") (name "Net-(IC3B-+IN)") (class "Default")
      (node (ref "IC3") (pin "5") (pinfunction "+IN_5") (pintype "input"))
      (node (ref "R1") (pin "2B") (pinfunction "2B_2B") (pintype "passive"))
    )
    (net (code "12") (name "Net-(IC3B--IN)") (class "Default")
      (node (ref "IC3") (pin "6") (pinfunction "-IN_6") (pintype "input"))
      (node (ref "R21") (pin "1") (pinfunction "1_1") (pintype "passive"))
      (node (ref "R22") (pin "2") (pinfunction "2_2") (pintype "passive"))
    )
    (net (code "13") (name "Net-(IC3B-OUT)") (class "Default")
      (node (ref "C41") (pin "+") (pinfunction "+_+") (pintype "passive"))
      (node (ref "C43") (pin "1") (pinfunction "1_1") (pintype "passive"))
      (node (ref "IC3") (pin "7") (pinfunction "OUT_7") (pintype "output"))
      (node (ref "R41") (pin "2") (pinfunction "2_2") (pintype "passive"))
    )
    (net (code "14") (name "Net-(IC4A--IN)") (class "Default")
      (node (ref "IC4") (pin "1") (pinfunction "OUT_1") (pintype "output"))
      (node (ref "IC4") (pin "2") (pinfunction "-IN_2") (pintype "input"))
      (node (ref "R10") (pin "1") (pinfunction "1_1") (pintype "passive"))
    )
    (net (code "15") (name "Net-(IC4B--IN)") (class "Default")
      (node (ref "IC4") (pin "6") (pinfunction "-IN_6") (pintype "input"))
      (node (ref "IC4") (pin "7") (pinfunction "OUT_7") (pintype "output"))
      (node (ref "R11") (pin "1") (pinfunction "1_1") (pintype "passive"))
    )
    (net (code "16") (name "Net-(IC5A--IN)") (class "Default")
      (node (ref "IC5") (pin "1") (pinfunction "OUT_1") (pintype "output"))
      (node (ref "IC5") (pin "2") (pinfunction "-IN_2") (pintype "input"))
      (node (ref "R12") (pin "1") (pinfunction "1_1") (pintype "passive"))
    )
    (net (code "17") (name "Net-(IC5B--IN)") (class "Default")
      (node (ref "IC5") (pin "6") (pinfunction "-IN_6") (pintype "input"))
      (node (ref "IC5") (pin "7") (pinfunction "OUT_7") (pintype "output"))
      (node (ref "R13") (pin "1") (pinfunction "1_1") (pintype "passive"))
    )
    (net (code "18") (name "Net-(IC6A--IN)") (class "Default")
      (node (ref "IC6") (pin "1") (pinfunction "OUT_1") (pintype "output"))
      (node (ref "IC6") (pin "2") (pinfunction "-IN_2") (pintype "input"))
      (node (ref "R14") (pin "1") (pinfunction "1_1") (pintype "passive"))
    )
    (net (code "19") (name "Net-(IC6B--IN)") (class "Default")
      (node (ref "IC6") (pin "6") (pinfunction "-IN_6") (pintype "input"))
      (node (ref "IC6") (pin "7") (pinfunction "OUT_7") (pintype "output"))
      (node (ref "R15") (pin "1") (pinfunction "1_1") (pintype "passive"))
    )
    (net (code "20") (name "Net-(IC7A--IN)") (class "Default")
      (node (ref "IC7") (pin "1") (pinfunction "OUT_1") (pintype "output"))
      (node (ref "IC7") (pin "2") (pinfunction "-IN_2") (pintype "input"))
      (node (ref "R16") (pin "1") (pinfunction "1_1") (pintype "passive"))
    )
    (net (code "21") (name "Net-(IC7B--IN)") (class "Default")
      (node (ref "IC7") (pin "6") (pinfunction "-IN_6") (pintype "input"))
      (node (ref "IC7") (pin "7") (pinfunction "OUT_7") (pintype "output"))
      (node (ref "R17") (pin "1") (pinfunction "1_1") (pintype "passive"))
    )
    (net (code "22") (name "Net-(IC8A--IN)") (class "Default")
      (node (ref "IC8") (pin "1") (pinfunction "OUT_1") (pintype "output"))
      (node (ref "IC8") (pin "2") (pinfunction "-IN_2") (pintype "input"))
      (node (ref "R9") (pin "1") (pinfunction "1_1") (pintype "passive"))
    )
    (net (code "23") (name "Net-(IC8B--IN)") (class "Default")
      (node (ref "IC8") (pin "6") (pinfunction "-IN_6") (pintype "input"))
      (node (ref "IC8") (pin "7") (pinfunction "OUT_7") (pintype "output"))
      (node (ref "R18") (pin "1") (pinfunction "1_1") (pintype "passive"))
    )
    (net (code "24") (name "Net-(IC9A--IN)") (class "Default")
      (node (ref "IC9") (pin "1") (pinfunction "OUT_1") (pintype "output"))
      (node (ref "IC9") (pin "2") (pinfunction "-IN_2") (pintype "input"))
      (node (ref "R19") (pin "1") (pinfunction "1_1") (pintype "passive"))
    )
    (net (code "25") (name "Net-(IC9B--IN)") (class "Default")
      (node (ref "IC9") (pin "6") (pinfunction "-IN_6") (pintype "input"))
      (node (ref "IC9") (pin "7") (pinfunction "OUT_7") (pintype "output"))
      (node (ref "R20") (pin "1") (pinfunction "1_1") (pintype "passive"))
    )
    (net (code "26") (name "Net-(IC10A--IN)") (class "Default")
      (node (ref "IC10") (pin "1") (pinfunction "OUT_1") (pintype "output"))
      (node (ref "IC10") (pin "2") (pinfunction "-IN_2") (pintype "input"))
      (node (ref "R45") (pin "1") (pinfunction "1_1") (pintype "passive"))
    )
    (net (code "27") (name "Net-(IC10B--IN)") (class "Default")
      (node (ref "IC10") (pin "6") (pinfunction "-IN_6") (pintype "input"))
      (node (ref "IC10") (pin "7") (pinfunction "OUT_7") (pintype "output"))
      (node (ref "R46") (pin "1") (pinfunction "1_1") (pintype "passive"))
    )
    (net (code "28") (name "Net-(IC11A--IN)") (class "Default")
      (node (ref "IC11") (pin "1") (pinfunction "OUT_1") (pintype "output"))
      (node (ref "IC11") (pin "2") (pinfunction "-IN_2") (pintype "input"))
      (node (ref "R23") (pin "1") (pinfunction "1_1") (pintype "passive"))
    )
    (net (code "29") (name "Net-(IC11B--IN)") (class "Default")
      (node (ref "IC11") (pin "6") (pinfunction "-IN_6") (pintype "input"))
      (node (ref "IC11") (pin "7") (pinfunction "OUT_7") (pintype "output"))
      (node (ref "R24") (pin "1") (pinfunction "1_1") (pintype "passive"))
    )
    (net (code "30") (name "Net-(IC12A--IN)") (class "Default")
      (node (ref "IC12") (pin "1") (pinfunction "OUT_1") (pintype "output"))
      (node (ref "IC12") (pin "2") (pinfunction "-IN_2") (pintype "input"))
      (node (ref "R25") (pin "1") (pinfunction "1_1") (pintype "passive"))
    )
    (net (code "31") (name "Net-(IC12B--IN)") (class "Default")
      (node (ref "IC12") (pin "6") (pinfunction "-IN_6") (pintype "input"))
      (node (ref "IC12") (pin "7") (pinfunction "OUT_7") (pintype "output"))
      (node (ref "R26") (pin "1") (pinfunction "1_1") (pintype "passive"))
    )
    (net (code "32") (name "Net-(IC13A--IN)") (class "Default")
      (node (ref "IC13") (pin "1") (pinfunction "OUT_1") (pintype "output"))
      (node (ref "IC13") (pin "2") (pinfunction "-IN_2") (pintype "input"))
      (node (ref "R27") (pin "1") (pinfunction "1_1") (pintype "passive"))
    )
    (net (code "33") (name "Net-(IC13B--IN)") (class "Default")
      (node (ref "IC13") (pin "6") (pinfunction "-IN_6") (pintype "input"))
      (node (ref "IC13") (pin "7") (pinfunction "OUT_7") (pintype "output"))
      (node (ref "R28") (pin "1") (pinfunction "1_1") (pintype "passive"))
    )
    (net (code "34") (name "Net-(IC14A--IN)") (class "Default")
      (node (ref "IC14") (pin "1") (pinfunction "OUT_1") (pintype "output"))
      (node (ref "IC14") (pin "2") (pinfunction "-IN_2") (pintype "input"))
      (node (ref "R29") (pin "1") (pinfunction "1_1") (pintype "passive"))
    )
    (net (code "35") (name "Net-(IC14B--IN)") (class "Default")
      (node (ref "IC14") (pin "6") (pinfunction "-IN_6") (pintype "input"))
      (node (ref "IC14") (pin "7") (pinfunction "OUT_7") (pintype "output"))
      (node (ref "R30") (pin "1") (pinfunction "1_1") (pintype "passive"))
    )
    (net (code "36") (name "Net-(IC15A--IN)") (class "Default")
      (node (ref "IC15") (pin "1") (pinfunction "OUT_1") (pintype "output"))
      (node (ref "IC15") (pin "2") (pinfunction "-IN_2") (pintype "input"))
      (node (ref "R31") (pin "1") (pinfunction "1_1") (pintype "passive"))
    )
    (net (code "37") (name "Net-(IC15B--IN)") (class "Default")
      (node (ref "IC15") (pin "6") (pinfunction "-IN_6") (pintype "input"))
      (node (ref "IC15") (pin "7") (pinfunction "OUT_7") (pintype "output"))
      (node (ref "R32") (pin "1") (pinfunction "1_1") (pintype "passive"))
    )
    (net (code "38") (name "Net-(IC16A--IN)") (class "Default")
      (node (ref "IC16") (pin "1") (pinfunction "OUT_1") (pintype "output"))
      (node (ref "IC16") (pin "2") (pinfunction "-IN_2") (pintype "input"))
      (node (ref "R33") (pin "1") (pinfunction "1_1") (pintype "passive"))
    )
    (net (code "39") (name "Net-(IC16B--IN)") (class "Default")
      (node (ref "IC16") (pin "6") (pinfunction "-IN_6") (pintype "input"))
      (node (ref "IC16") (pin "7") (pinfunction "OUT_7") (pintype "output"))
      (node (ref "R34") (pin "1") (pinfunction "1_1") (pintype "passive"))
    )
    (net (code "40") (name "Net-(IC17A--IN)") (class "Default")
      (node (ref "IC17") (pin "1") (pinfunction "OUT_1") (pintype "output"))
      (node (ref "IC17") (pin "2") (pinfunction "-IN_2") (pintype "input"))
      (node (ref "R47") (pin "1") (pinfunction "1_1") (pintype "passive"))
    )
    (net (code "41") (name "Net-(IC17B--IN)") (class "Default")
      (node (ref "IC17") (pin "6") (pinfunction "-IN_6") (pintype "input"))
      (node (ref "IC17") (pin "7") (pinfunction "OUT_7") (pintype "output"))
      (node (ref "R48") (pin "1") (pinfunction "1_1") (pintype "passive"))
    )
    (net (code "42") (name "Net-(IC18A--IN)") (class "Default")
      (node (ref "IC18") (pin "1") (pinfunction "OUT_1") (pintype "output"))
      (node (ref "IC18") (pin "2") (pinfunction "-IN_2") (pintype "input"))
      (node (ref "R49") (pin "1") (pinfunction "1_1") (pintype "passive"))
    )
    (net (code "43") (name "Net-(IC18B--IN)") (class "Default")
      (node (ref "IC18") (pin "6") (pinfunction "-IN_6") (pintype "input"))
      (node (ref "IC18") (pin "7") (pinfunction "OUT_7") (pintype "output"))
      (node (ref "R50") (pin "1") (pinfunction "1_1") (pintype "passive"))
    )
    (net (code "44") (name "Net-(IC19A--IN)") (class "Default")
      (node (ref "IC19") (pin "1") (pinfunction "OUT_1") (pintype "output"))
      (node (ref "IC19") (pin "2") (pinfunction "-IN_2") (pintype "input"))
      (node (ref "R51") (pin "1") (pinfunction "1_1") (pintype "passive"))
    )
    (net (code "45") (name "Net-(IC19B--IN)") (class "Default")
      (node (ref "IC19") (pin "6") (pinfunction "-IN_6") (pintype "input"))
      (node (ref "IC19") (pin "7") (pinfunction "OUT_7") (pintype "output"))
      (node (ref "R52") (pin "1") (pinfunction "1_1") (pintype "passive"))
    )
    (net (code "46") (name "Net-(LED1-PadA)") (class "Default")
      (node (ref "LED1") (pin "A") (pinfunction "A_A") (pintype "passive"))
      (node (ref "R5") (pin "1") (pinfunction "1_1") (pintype "passive"))
    )
    (net (code "47") (name "Net-(LED2-C)") (class "Default")
      (node (ref "LED2") (pin "K") (pinfunction "C_K") (pintype "passive"))
      (node (ref "R6") (pin "1") (pinfunction "1_1") (pintype "passive"))
    )
    (net (code "48") (name "Net-(R1-Pad3A)") (class "Default")
      (node (ref "R1") (pin "3A") (pinfunction "3A_3A") (pintype "passive"))
      (node (ref "SV2") (pin "1") (pinfunction "1_1") (pintype "passive"))
    )
    (net (code "49") (name "Net-(R1-Pad3B)") (class "Default")
      (node (ref "R1") (pin "3B") (pinfunction "3B_3B") (pintype "passive"))
      (node (ref "SV2") (pin "2") (pinfunction "2_2") (pintype "passive"))
    )
    (net (code "50") (name "Net-(R21-Pad2)") (class "Default")
      (node (ref "R21") (pin "2") (pinfunction "2_2") (pintype "passive"))
      (node (ref "R41") (pin "1") (pinfunction "1_1") (pintype "passive"))
      (node (ref "R43") (pin "2") (pinfunction "2_2") (pintype "passive"))
    )
    (net (code "51") (name "Net-(R42-Pad1)") (class "Default")
      (node (ref "R42") (pin "1") (pinfunction "1_1") (pintype "passive"))
      (node (ref "R44") (pin "2") (pinfunction "2_2") (pintype "passive"))
      (node (ref "R7") (pin "2") (pinfunction "2_2") (pintype "passive"))
    )
    (net (code "52") (name "OUT_L") (class "Default")
      (node (ref "C60") (pin "+") (pinfunction "+_+") (pintype "passive"))
      (node (ref "R10") (pin "2") (pinfunction "2_2") (pintype "passive"))
      (node (ref "R11") (pin "2") (pinfunction "2_2") (pintype "passive"))
      (node (ref "R12") (pin "2") (pinfunction "2_2") (pintype "passive"))
      (node (ref "R13") (pin "2") (pinfunction "2_2") (pintype "passive"))
      (node (ref "R14") (pin "2") (pinfunction "2_2") (pintype "passive"))
      (node (ref "R15") (pin "2") (pinfunction "2_2") (pintype "passive"))
      (node (ref "R16") (pin "2") (pinfunction "2_2") (pintype "passive"))
      (node (ref "R17") (pin "2") (pinfunction "2_2") (pintype "passive"))
      (node (ref "R18") (pin "2") (pinfunction "2_2") (pintype "passive"))
      (node (ref "R19") (pin "2") (pinfunction "2_2") (pintype "passive"))
      (node (ref "R20") (pin "2") (pinfunction "2_2") (pintype "passive"))
      (node (ref "R43") (pin "1") (pinfunction "1_1") (pintype "passive"))
      (node (ref "R45") (pin "2") (pinfunction "2_2") (pintype "passive"))
      (node (ref "R46") (pin "2") (pinfunction "2_2") (pintype "passive"))
      (node (ref "R47") (pin "2") (pinfunction "2_2") (pintype "passive"))
      (node (ref "R48") (pin "2") (pinfunction "2_2") (pintype "passive"))
      (node (ref "R9") (pin "2") (pinfunction "2_2") (pintype "passive"))
      (node (ref "SV1") (pin "3") (pinfunction "3_3") (pintype "passive"))
    )
    (net (code "53") (name "OUT_R") (class "Default")
      (node (ref "C59") (pin "+") (pinfunction "+_+") (pintype "passive"))
      (node (ref "R23") (pin "2") (pinfunction "2_2") (pintype "passive"))
      (node (ref "R24") (pin "2") (pinfunction "2_2") (pintype "passive"))
      (node (ref "R25") (pin "2") (pinfunction "2_2") (pintype "passive"))
      (node (ref "R26") (pin "2") (pinfunction "2_2") (pintype "passive"))
      (node (ref "R27") (pin "2") (pinfunction "2_2") (pintype "passive"))
      (node (ref "R28") (pin "2") (pinfunction "2_2") (pintype "passive"))
      (node (ref "R29") (pin "2") (pinfunction "2_2") (pintype "passive"))
      (node (ref "R30") (pin "2") (pinfunction "2_2") (pintype "passive"))
      (node (ref "R31") (pin "2") (pinfunction "2_2") (pintype "passive"))
      (node (ref "R32") (pin "2") (pinfunction "2_2") (pintype "passive"))
      (node (ref "R33") (pin "2") (pinfunction "2_2") (pintype "passive"))
      (node (ref "R34") (pin "2") (pinfunction "2_2") (pintype "passive"))
      (node (ref "R44") (pin "1") (pinfunction "1_1") (pintype "passive"))
      (node (ref "R49") (pin "2") (pinfunction "2_2") (pintype "passive"))
      (node (ref "R50") (pin "2") (pinfunction "2_2") (pintype "passive"))
      (node (ref "R51") (pin "2") (pinfunction "2_2") (pintype "passive"))
      (node (ref "R52") (pin "2") (pinfunction "2_2") (pintype "passive"))
      (node (ref "SV1") (pin "2") (pinfunction "2_2") (pintype "passive"))
    )
    (net (code "54") (name "unconnected-(X3-PadB)") (class "Default")
      (node (ref "X3") (pin "B") (pinfunction "B_B") (pintype "passive"))
    )
  )
)
